# BMS-S03-V01-CellInterface.net
KiCad netlist of a schematic drawn in Altium Designer
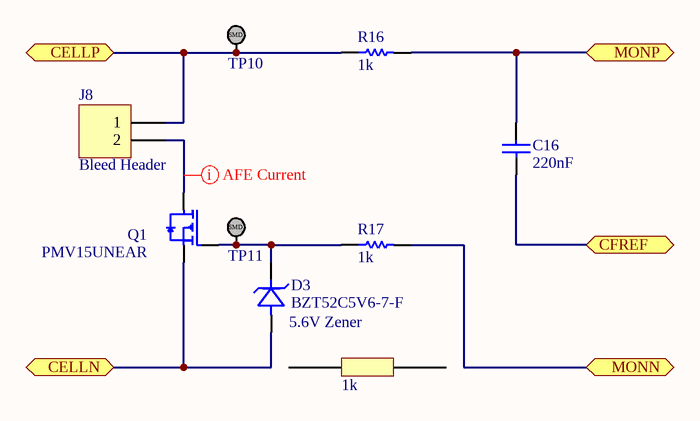
[diagram p0: BMS-S03-V01-CellInterface.SchDoc]

(export (version "E")
  (design (tool "Eeschema 10.0.6"))
  (components
    (comp (ref "C16")
      (value "220nF")
      (footprint "Cap_Ceramic_0603")
      (description "Capacitor, Ceramic, SMD, 220nF, 50V, 5%, X7R, 0603")
      (libsource (lib "StandardCapacitors") (part "220nF 50V 5% X7R 0603"))
    )
    (comp (ref "D3")
      (value "BZT52C5V6-7-F")
      (footprint "SOD123")
      (description "Diode, SMD, Zender, 5.6V, 7%, 500mW, SOD-123")
      (fields (field (name "MANUFACTURER") "Generic") (field (name "MPN") "1.8V 500mW"))
      (libsource (lib "QUTMS_DiodeLibrary") (part "BZT52C5V6-7-F"))
    )
    (comp (ref "J8")
      (value "Bleed Header")
      (footprint "HDR1X2")
      (description "Header, 2-Pin")
      (fields (field (name "PUBLISHER") "Altium Limited"))
      (libsource (lib "Miscellaneous Connectors") (part "Header 2"))
    )
    (comp (ref "Q1")
      (value "MOSFET N")
      (footprint "PMV15UNEAR")
      (description "MOSFET N-CH, 20V, SOT23")
      (fields (field (name "MANUFACTURER") "Nexperia") (field (name "MANUFACTURER PART NUMBER") "PMV15UNEAR"))
      (libsource (lib "CellMonitor") (part "PMV15UNEAR"))
    )
    (comp (ref "R16")
      (value "1k")
      (footprint "Res_ThinFilm_0603")
      (description "Resistor, SMD, 1k, 0.1W, 5%, 0603")
      (libsource (lib "StandardResistors") (part "1k 5% 0603"))
    )
    (comp (ref "R17")
      (value "1k")
      (footprint "Res_ThinFilm_0603")
      (description "Resistor, SMD, 1k, 0.1W, 5%, 0603")
      (libsource (lib "StandardResistors") (part "1k 5% 0603"))
    )
    (comp (ref "TP10")
      (value "TestPoint_SMD")
      (footprint "TestPointSMD")
      (libsource (lib "StandardTest") (part "TestPoint_SMD"))
    )
    (comp (ref "TP11")
      (value "TestPoint_SMD")
      (footprint "TestPointSMD")
      (libsource (lib "StandardTest") (part "TestPoint_SMD"))
    )
  )
  (nets
    (net (code "1") (name "/CELLN") (class "Default")
      (node (ref "D3") (pin "A") (pinfunction "Anode_A") (pintype "passive"))
      (node (ref "Q1") (pin "S") (pinfunction "Source_S") (pintype "passive"))
    )
    (net (code "2") (name "/CELLP") (class "Default")
      (node (ref "J8") (pin "1") (pinfunction "1_1") (pintype "passive"))
      (node (ref "R16") (pin "1") (pinfunction "1_1") (pintype "passive"))
      (node (ref "TP10") (pin "1") (pinfunction "1_1") (pintype "passive"))
    )
    (net (code "3") (name "/CFREF") (class "Default")
      (node (ref "C16") (pin "1") (pinfunction "1_1") (pintype "passive"))
    )
    (net (code "4") (name "/MONN") (class "Default")
      (node (ref "R17") (pin "2") (pinfunction "2_2") (pintype "passive"))
    )
    (net (code "5") (name "/MONP") (class "Default")
      (node (ref "C16") (pin "2") (pinfunction "2_2") (pintype "passive"))
      (node (ref "R16") (pin "2") (pinfunction "2_2") (pintype "passive"))
    )
    (net (code "6") (name "Net-(D3-Cathode)") (class "Default")
      (node (ref "D3") (pin "K") (pinfunction "Cathode_K") (pintype "passive"))
      (node (ref "Q1") (pin "G") (pinfunction "Gate_G") (pintype "passive"))
      (node (ref "R17") (pin "1") (pinfunction "1_1") (pintype "passive"))
      (node (ref "TP11") (pin "1") (pinfunction "1_1") (pintype "passive"))
    )
    (net (code "7") (name "Net-(Q1-Drain)") (class "Default")
      (node (ref "J8") (pin "2") (pinfunction "2_2") (pintype "passive"))
      (node (ref "Q1") (pin "D") (pinfunction "Drain_D") (pintype "passive"))
    )
  )
)
